# Analog_Signal_Conditioner_V2.net
KiCad netlist of a schematic drawn in Altium Designer
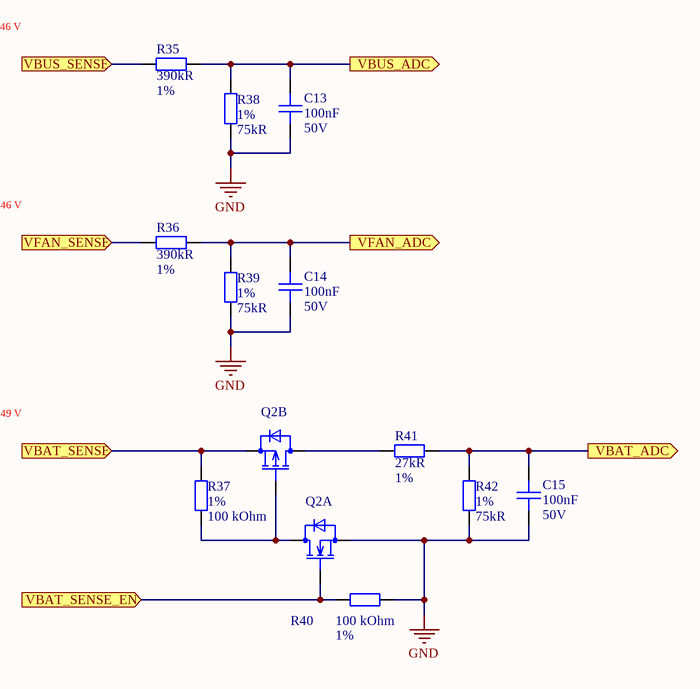
[diagram p0: Analog_Signal_Conditioner_V2.SchDoc]

(export (version "E")
  (design (tool "Eeschema 10.0.6"))
  (components
    (comp (ref "C13")
      (value "CAP CER 0.1UF 50V X7R 0402")
      (footprint "C0402")
      (description "0.1µF ±10% 50V Ceramic Capacitor X7R 0402 (1005 Metric)")
      (fields
        (field (name "MANUFACTURER PART NUMBER") "CGA2B3X7R1H104K050BB")
        (field (name "MANUFACTURER") "TDK")
        (field (name "CAPACITANCE") "100nF")
        (field (name "VOLTAGE") "50V")
      )
      (libsource (lib "capacitors_smd") (part "CAP CER 0.1UF 50V X7R 0402"))
    )
    (comp (ref "C14")
      (value "CAP CER 0.1UF 50V X7R 0402")
      (footprint "C0402")
      (description "0.1µF ±10% 50V Ceramic Capacitor X7R 0402 (1005 Metric)")
      (fields
        (field (name "MANUFACTURER PART NUMBER") "CGA2B3X7R1H104K050BB")
        (field (name "MANUFACTURER") "TDK")
        (field (name "CAPACITANCE") "100nF")
        (field (name "VOLTAGE") "50V")
      )
      (libsource (lib "capacitors_smd") (part "CAP CER 0.1UF 50V X7R 0402"))
    )
    (comp (ref "C15")
      (value "CAP CER 0.1UF 50V X7R 0402")
      (footprint "C0402")
      (description "0.1µF ±10% 50V Ceramic Capacitor X7R 0402 (1005 Metric)")
      (fields
        (field (name "MANUFACTURER PART NUMBER") "CGA2B3X7R1H104K050BB")
        (field (name "MANUFACTURER") "TDK")
        (field (name "CAPACITANCE") "100nF")
        (field (name "VOLTAGE") "50V")
      )
      (libsource (lib "capacitors_smd") (part "CAP CER 0.1UF 50V X7R 0402"))
    )
    (comp (ref "Q2")
      (value "EM6M2T2R")
      (footprint "SON_400UV-7_DIO")
      (description "Mosfet Array N and P-Channel 20V 200mA 150mW Surface Mount EMT6")
      (fields (field (name "MANUFACTURER") "Rohm"))
      (libsource (lib "mosfets") (part "ARRAY MOSFET N/P-CH 20V 0.2A EMT6"))
    )
    (comp (ref "R35")
      (value "RES SMD 390K OHM 1% 1/16W 0402")
      (footprint "R0402")
      (description "390 kOhms ±1% 0.063W, 1/16W Chip Resistor 0402 (1005 Metric) Moisture Resistant Thick Film")
      (fields
        (field (name "MANUFACTURER") "Yageo")
        (field (name "MANUFACTURER PART NUMBER") "RC0402FR-07390KL")
        (field (name "RESISTANCE") "390kR")
        (field (name "TOLERANCE") "1%")
      )
      (libsource (lib "resistors_smd") (part "RES SMD 390K OHM 1% 1/16W 0402"))
    )
    (comp (ref "R36")
      (value "RES SMD 390K OHM 1% 1/16W 0402")
      (footprint "R0402")
      (description "390 kOhms ±1% 0.063W, 1/16W Chip Resistor 0402 (1005 Metric) Moisture Resistant Thick Film")
      (fields
        (field (name "MANUFACTURER") "Yageo")
        (field (name "MANUFACTURER PART NUMBER") "RC0402FR-07390KL")
        (field (name "RESISTANCE") "390kR")
        (field (name "TOLERANCE") "1%")
      )
      (libsource (lib "resistors_smd") (part "RES SMD 390K OHM 1% 1/16W 0402"))
    )
    (comp (ref "R37")
      (value "RES SMD 100K OHM 1% 1/16W 0402")
      (footprint "R0402")
      (description "100 kOhms ±1% 0.063W, 1/16W Chip Resistor 0402 (1005 Metric) Moisture Resistant Thick Film")
      (fields
        (field (name "MANUFACTURER") "Yageo")
        (field (name "MANUFACTURER PART NUMBER") "RC0402FR-07100KL")
        (field (name "TOLERANCE") "1%")
        (field (name "RESISTANCE") "100 kOhm")
      )
      (libsource (lib "resistors_smd") (part "RES SMD 100K OHM 1% 1/16W 0402"))
    )
    (comp (ref "R38")
      (value "RES SMD 75K OHM 1% 1/16W 0402")
      (footprint "R0402")
      (description "75 kOhms ±1% 0.063W, 1/16W Chip Resistor 0402 (1005 Metric) Automotive AEC-Q200 Thick Film")
      (fields
        (field (name "MANUFACTURER") "Stackpole Electronics")
        (field (name "MANUFACTURER PART NUMBER") "RMCF0402FT75K0")
        (field (name "TOLERANCE") "1%")
        (field (name "RESISTANCE") "75kR")
      )
      (libsource (lib "resistors_smd") (part "RES SMD 75K OHM 1% 1/16W 0402"))
    )
    (comp (ref "R39")
      (value "RES SMD 75K OHM 1% 1/16W 0402")
      (footprint "R0402")
      (description "75 kOhms ±1% 0.063W, 1/16W Chip Resistor 0402 (1005 Metric) Automotive AEC-Q200 Thick Film")
      (fields
        (field (name "MANUFACTURER") "Stackpole Electronics")
        (field (name "MANUFACTURER PART NUMBER") "RMCF0402FT75K0")
        (field (name "TOLERANCE") "1%")
        (field (name "RESISTANCE") "75kR")
      )
      (libsource (lib "resistors_smd") (part "RES SMD 75K OHM 1% 1/16W 0402"))
    )
    (comp (ref "R40")
      (value "RES SMD 100K OHM 1% 1/16W 0402")
      (footprint "R0402")
      (description "100 kOhms ±1% 0.063W, 1/16W Chip Resistor 0402 (1005 Metric) Moisture Resistant Thick Film")
      (fields
        (field (name "MANUFACTURER") "Yageo")
        (field (name "MANUFACTURER PART NUMBER") "RC0402FR-07100KL")
        (field (name "TOLERANCE") "1%")
        (field (name "RESISTANCE") "100 kOhm")
      )
      (libsource (lib "") (part "RES SMD 100K OHM 1% 1/16W 0402_1"))
    )
    (comp (ref "R41")
      (value "RES SMD 27K OHM 1% 1/16W 0402")
      (footprint "R0402")
      (description "27 kOhms ±1% 0.063W, 1/16W Chip Resistor 0402 (1005 Metric) Moisture Resistant Thick Film")
      (fields
        (field (name "MANUFACTURER") "Yageo")
        (field (name "MANUFACTURER PART NUMBER") "RC0402FR-0727KL")
        (field (name "RESISTANCE") "27kR")
        (field (name "TOLERANCE") "1%")
      )
      (libsource (lib "resistors_smd") (part "RES SMD 27K OHM 1% 1/16W 0402"))
    )
    (comp (ref "R42")
      (value "RES SMD 75K OHM 1% 1/16W 0402")
      (footprint "R0402")
      (description "75 kOhms ±1% 0.063W, 1/16W Chip Resistor 0402 (1005 Metric) Automotive AEC-Q200 Thick Film")
      (fields
        (field (name "MANUFACTURER") "Stackpole Electronics")
        (field (name "MANUFACTURER PART NUMBER") "RMCF0402FT75K0")
        (field (name "TOLERANCE") "1%")
        (field (name "RESISTANCE") "75kR")
      )
      (libsource (lib "resistors_smd") (part "RES SMD 75K OHM 1% 1/16W 0402"))
    )
  )
  (nets
    (net (code "1") (name "/VBAT_ADC") (class "Default")
      (node (ref "C15") (pin "2") (pinfunction "2_2") (pintype "passive"))
      (node (ref "R41") (pin "2") (pinfunction "2_2") (pintype "passive"))
      (node (ref "R42") (pin "2") (pinfunction "2_2") (pintype "passive"))
    )
    (net (code "2") (name "/VBAT_SENSE") (class "Default")
      (node (ref "Q2") (pin "4") (pinfunction "S_4") (pintype "passive"))
      (node (ref "R37") (pin "2") (pinfunction "2_2") (pintype "passive"))
    )
    (net (code "3") (name "/VBAT_SENSE_EN") (class "Default")
      (node (ref "Q2") (pin "2") (pinfunction "G_2") (pintype "passive"))
      (node (ref "R40") (pin "2") (pinfunction "2_2") (pintype "passive"))
    )
    (net (code "4") (name "/VBUS_ADC") (class "Default")
      (node (ref "C13") (pin "2") (pinfunction "2_2") (pintype "passive"))
      (node (ref "R35") (pin "2") (pinfunction "2_2") (pintype "passive"))
      (node (ref "R38") (pin "2") (pinfunction "2_2") (pintype "passive"))
    )
    (net (code "5") (name "/VBUS_SENSE") (class "Default")
      (node (ref "R35") (pin "1") (pinfunction "1_1") (pintype "passive"))
    )
    (net (code "6") (name "/VFAN_ADC") (class "Default")
      (node (ref "C14") (pin "2") (pinfunction "2_2") (pintype "passive"))
      (node (ref "R36") (pin "2") (pinfunction "2_2") (pintype "passive"))
      (node (ref "R39") (pin "2") (pinfunction "2_2") (pintype "passive"))
    )
    (net (code "7") (name "/VFAN_SENSE") (class "Default")
      (node (ref "R36") (pin "1") (pinfunction "1_1") (pintype "passive"))
    )
    (net (code "8") (name "GND") (class "Default")
      (node (ref "C13") (pin "1") (pinfunction "1_1") (pintype "passive"))
      (node (ref "C14") (pin "1") (pinfunction "1_1") (pintype "passive"))
      (node (ref "C15") (pin "1") (pinfunction "1_1") (pintype "passive"))
      (node (ref "Q2") (pin "1") (pinfunction "S_1") (pintype "passive"))
      (node (ref "R38") (pin "1") (pinfunction "1_1") (pintype "passive"))
      (node (ref "R39") (pin "1") (pinfunction "1_1") (pintype "passive"))
      (node (ref "R40") (pin "1") (pinfunction "1_1") (pintype "passive"))
      (node (ref "R42") (pin "1") (pinfunction "1_1") (pintype "passive"))
    )
    (net (code "9") (name "Net-(Q2A-D)") (class "Default")
      (node (ref "Q2") (pin "5") (pinfunction "G_5") (pintype "passive"))
      (node (ref "Q2") (pin "6") (pinfunction "D_6") (pintype "passive"))
      (node (ref "R37") (pin "1") (pinfunction "1_1") (pintype "passive"))
    )
    (net (code "10") (name "Net-(Q2B-D)") (class "Default")
      (node (ref "Q2") (pin "3") (pinfunction "D_3") (pintype "passive"))
      (node (ref "R41") (pin "1") (pinfunction "1_1") (pintype "passive"))
    )
  )
)
